# CEF_Contor.net
KiCad netlist of a schematic drawn in Altium Designer
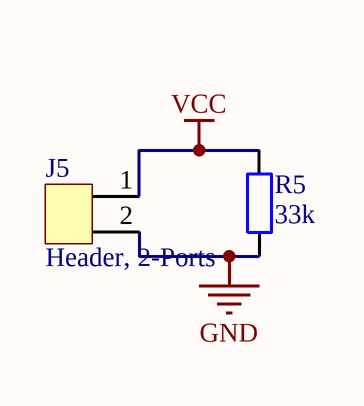
[diagram p0: CEF Contor.SchDoc]

(export (version "E")
  (design (tool "Eeschema 10.0.6"))
  (components
    (comp (ref "J5")
      (value "Header, 2-Ports")
      (footprint "HDR_1X2_TE")
      (description "Connector, 2-Ports")
      (libsource (lib "CEF") (part "CON_1x2"))
    )
    (comp (ref "R5")
      (value "33k")
      (footprint "Resistor")
      (description "0.25W,Axial")
      (libsource (lib "CEF") (part "Resistor 0.25W 5mm"))
    )
  )
  (nets
    (net (code "1") (name "GND") (class "Default")
      (node (ref "J5") (pin "2") (pinfunction "2_2") (pintype "passive"))
      (node (ref "R5") (pin "1") (pinfunction "1_1") (pintype "passive"))
    )
    (net (code "2") (name "VCC") (class "Default")
      (node (ref "J5") (pin "1") (pinfunction "1_1") (pintype "passive"))
      (node (ref "R5") (pin "2") (pinfunction "2_2") (pintype "passive"))
    )
  )
)
